# Sheet2.net
KiCad netlist of a schematic drawn in Altium Designer
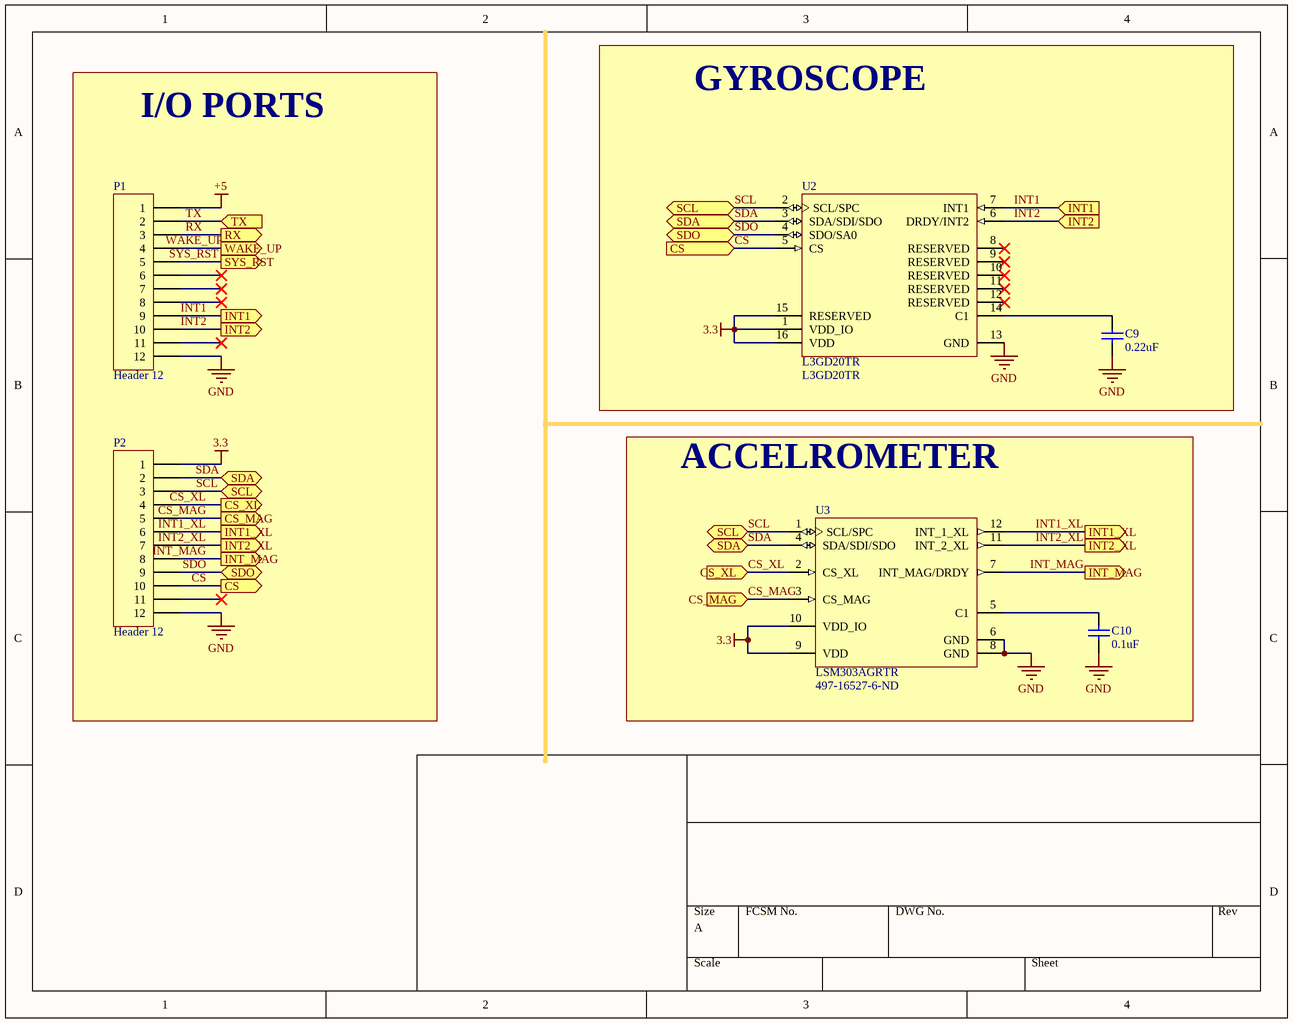
[diagram p0: Sheet2.SchDoc]

(export (version "E")
  (design (tool "Eeschema 10.0.6"))
  (components
    (comp (ref "C9")
      (value "0.22uF")
      (footprint "CAPC2013X140X50ML20T25")
      (description "CAP CER 0.22UF 25V X7R 0805")
      (fields
        (field (name "MANUFACTURER") "AVX Interconnect / Elco")
        (field (name "PART NUMBER") "08053C224JAT2A")
      )
      (libsource (lib "Integrated_Library1") (part "CAP SMD 0.22uF 0805"))
    )
    (comp (ref "C10")
      (value "0.1uF")
      (footprint "CAPC2013X135X45LL10T25")
      (description "Chip Capacitor, 0.1 uF, +/- 10%, 50 V, -55 to 125 degC, 0805 (2012 Metric), RoHS, Tape and Reel")
      (fields (field (name "VOLTAGE") "50V") (field (name "TOLERANCE") "10%"))
      (libsource (lib "Integrated_Library1") (part "CAP SMD 0.1uF 0805"))
    )
    (comp (ref "P1")
      (value "Header 12")
      (footprint "HDR1X12")
      (description "Header, 12-Pin")
      (fields (field (name "PUBLISHER") "Altium Limited"))
      (libsource (lib "Miscellaneous Connectors") (part "Header 12"))
    )
    (comp (ref "P2")
      (value "Header 12")
      (footprint "HDR1X12")
      (description "Header, 12-Pin")
      (fields (field (name "PUBLISHER") "Altium Limited"))
      (libsource (lib "Miscellaneous Connectors") (part "Header 12"))
    )
    (comp (ref "U2")
      (value "L3GD20TR")
      (footprint "STM-LGA16-4X4X1.1")
      (fields
        (field (name "MANUFACTURER") "STMicroelectronics")
        (field (name "SUPPLIER PART NUMBER 1") "L3GD20TR")
      )
      (libsource (lib "Schlib1") (part "GYROSCOPE"))
    )
    (comp (ref "U3")
      (value "LSM303AGRTR")
      (footprint "STM-LGA-12")
      (fields
        (field (name "MANUFACTURER") "STMicroelectronics")
        (field (name "SUPPLIER PART NUMBER 1") "497-16527-6-ND")
      )
      (libsource (lib "Integrated_Library1") (part "E-COMPASS"))
    )
  )
  (nets
    (net (code "1") (name "+5") (class "Default")
      (node (ref "P1") (pin "1") (pinfunction "1_1") (pintype "passive"))
    )
    (net (code "2") (name "/CS") (class "Default")
      (node (ref "P2") (pin "10") (pinfunction "10_10") (pintype "passive"))
      (node (ref "U2") (pin "5") (pinfunction "CS_5") (pintype "input"))
    )
    (net (code "3") (name "/CS_MAG") (class "Default")
      (node (ref "P2") (pin "5") (pinfunction "5_5") (pintype "passive"))
      (node (ref "U3") (pin "3") (pinfunction "CS_MAG_3") (pintype "input"))
    )
    (net (code "4") (name "/CS_XL") (class "Default")
      (node (ref "P2") (pin "4") (pinfunction "4_4") (pintype "passive"))
      (node (ref "U3") (pin "2") (pinfunction "CS_XL_2") (pintype "input"))
    )
    (net (code "5") (name "/INT1") (class "Default")
      (node (ref "P1") (pin "9") (pinfunction "9_9") (pintype "passive"))
      (node (ref "U2") (pin "7") (pinfunction "INT1_7") (pintype "input"))
    )
    (net (code "6") (name "/INT1_XL") (class "Default")
      (node (ref "P2") (pin "6") (pinfunction "6_6") (pintype "passive"))
      (node (ref "U3") (pin "12") (pinfunction "INT_1_XL_12") (pintype "output"))
    )
    (net (code "7") (name "/INT2") (class "Default")
      (node (ref "P1") (pin "10") (pinfunction "10_10") (pintype "passive"))
      (node (ref "U2") (pin "6") (pinfunction "DRDY/INT2_6") (pintype "input"))
    )
    (net (code "8") (name "/INT2_XL") (class "Default")
      (node (ref "P2") (pin "7") (pinfunction "7_7") (pintype "passive"))
      (node (ref "U3") (pin "11") (pinfunction "INT_2_XL_11") (pintype "output"))
    )
    (net (code "9") (name "/INT_MAG") (class "Default")
      (node (ref "P2") (pin "8") (pinfunction "8_8") (pintype "passive"))
      (node (ref "U3") (pin "7") (pinfunction "INT_MAG/DRDY_7") (pintype "output"))
    )
    (net (code "10") (name "/RX") (class "Default")
      (node (ref "P1") (pin "3") (pinfunction "3_3") (pintype "passive"))
    )
    (net (code "11") (name "/SCL") (class "Default")
      (node (ref "P2") (pin "3") (pinfunction "3_3") (pintype "passive"))
      (node (ref "U2") (pin "2") (pinfunction "SCL/SPC_2") (pintype "bidirectional"))
      (node (ref "U3") (pin "1") (pinfunction "SCL/SPC_1") (pintype "bidirectional"))
    )
    (net (code "12") (name "/SDA") (class "Default")
      (node (ref "P2") (pin "2") (pinfunction "2_2") (pintype "passive"))
      (node (ref "U2") (pin "3") (pinfunction "SDA/SDI/SDO_3") (pintype "bidirectional"))
      (node (ref "U3") (pin "4") (pinfunction "SDA/SDI/SDO_4") (pintype "bidirectional"))
    )
    (net (code "13") (name "/SDO") (class "Default")
      (node (ref "P2") (pin "9") (pinfunction "9_9") (pintype "passive"))
      (node (ref "U2") (pin "4") (pinfunction "SDO/SA0_4") (pintype "bidirectional"))
    )
    (net (code "14") (name "/SYS_RST") (class "Default")
      (node (ref "P1") (pin "5") (pinfunction "5_5") (pintype "passive"))
    )
    (net (code "15") (name "/TX") (class "Default")
      (node (ref "P1") (pin "2") (pinfunction "2_2") (pintype "passive"))
    )
    (net (code "16") (name "/WAKE_UP") (class "Default")
      (node (ref "P1") (pin "4") (pinfunction "4_4") (pintype "passive"))
    )
    (net (code "17") (name "3.3") (class "Default")
      (node (ref "P2") (pin "1") (pinfunction "1_1") (pintype "passive"))
      (node (ref "U2") (pin "1") (pinfunction "VDD_IO_1") (pintype "power_in"))
      (node (ref "U2") (pin "15") (pinfunction "RESERVED_15") (pintype "power_in"))
      (node (ref "U2") (pin "16") (pinfunction "VDD_16") (pintype "power_in"))
      (node (ref "U3") (pin "10") (pinfunction "VDD_IO_10") (pintype "power_in"))
      (node (ref "U3") (pin "9") (pinfunction "VDD_9") (pintype "power_in"))
    )
    (net (code "18") (name "GND") (class "Default")
      (node (ref "C10") (pin "1") (pinfunction "1_1") (pintype "passive"))
      (node (ref "C9") (pin "1") (pinfunction "1_1") (pintype "passive"))
      (node (ref "P1") (pin "12") (pinfunction "12_12") (pintype "passive"))
      (node (ref "P2") (pin "12") (pinfunction "12_12") (pintype "passive"))
      (node (ref "U2") (pin "13") (pinfunction "GND_13") (pintype "power_in"))
      (node (ref "U3") (pin "6") (pinfunction "GND_6") (pintype "power_in"))
      (node (ref "U3") (pin "8") (pinfunction "GND_8") (pintype "power_in"))
    )
    (net (code "19") (name "Net-(U2-C1)") (class "Default")
      (node (ref "C9") (pin "2") (pinfunction "2_2") (pintype "passive"))
      (node (ref "U2") (pin "14") (pinfunction "C1_14") (pintype "power_in"))
    )
    (net (code "20") (name "Net-(U3-C1)") (class "Default")
      (node (ref "C10") (pin "2") (pinfunction "2_2") (pintype "passive"))
      (node (ref "U3") (pin "5") (pinfunction "C1_5") (pintype "passive"))
    )
    (net (code "21") (name "unconnected-(P1-Pad6)") (class "Default")
      (node (ref "P1") (pin "6") (pinfunction "6_6") (pintype "passive+no_connect"))
    )
    (net (code "22") (name "unconnected-(P1-Pad7)") (class "Default")
      (node (ref "P1") (pin "7") (pinfunction "7_7") (pintype "passive+no_connect"))
    )
    (net (code "23") (name "unconnected-(P1-Pad8)") (class "Default")
      (node (ref "P1") (pin "8") (pinfunction "8_8") (pintype "passive+no_connect"))
    )
    (net (code "24") (name "unconnected-(P1-Pad11)") (class "Default")
      (node (ref "P1") (pin "11") (pinfunction "11_11") (pintype "passive+no_connect"))
    )
    (net (code "25") (name "unconnected-(P2-Pad11)") (class "Default")
      (node (ref "P2") (pin "11") (pinfunction "11_11") (pintype "passive+no_connect"))
    )
    (net (code "26") (name "unconnected-(U2-RESERVED-Pad8)") (class "Default")
      (node (ref "U2") (pin "8") (pinfunction "RESERVED_8") (pintype "power_in+no_connect"))
    )
    (net (code "27") (name "unconnected-(U2-RESERVED-Pad9)") (class "Default")
      (node (ref "U2") (pin "9") (pinfunction "RESERVED_9") (pintype "power_in+no_connect"))
    )
    (net (code "28") (name "unconnected-(U2-RESERVED-Pad10)") (class "Default")
      (node (ref "U2") (pin "10") (pinfunction "RESERVED_10") (pintype "power_in+no_connect"))
    )
    (net (code "29") (name "unconnected-(U2-RESERVED-Pad11)") (class "Default")
      (node (ref "U2") (pin "11") (pinfunction "RESERVED_11") (pintype "power_in+no_connect"))
    )
    (net (code "30") (name "unconnected-(U2-RESERVED-Pad12)") (class "Default")
      (node (ref "U2") (pin "12") (pinfunction "RESERVED_12") (pintype "power_in+no_connect"))
    )
  )
)
